# Sprite.net
KiCad netlist of a schematic drawn in EAGLE
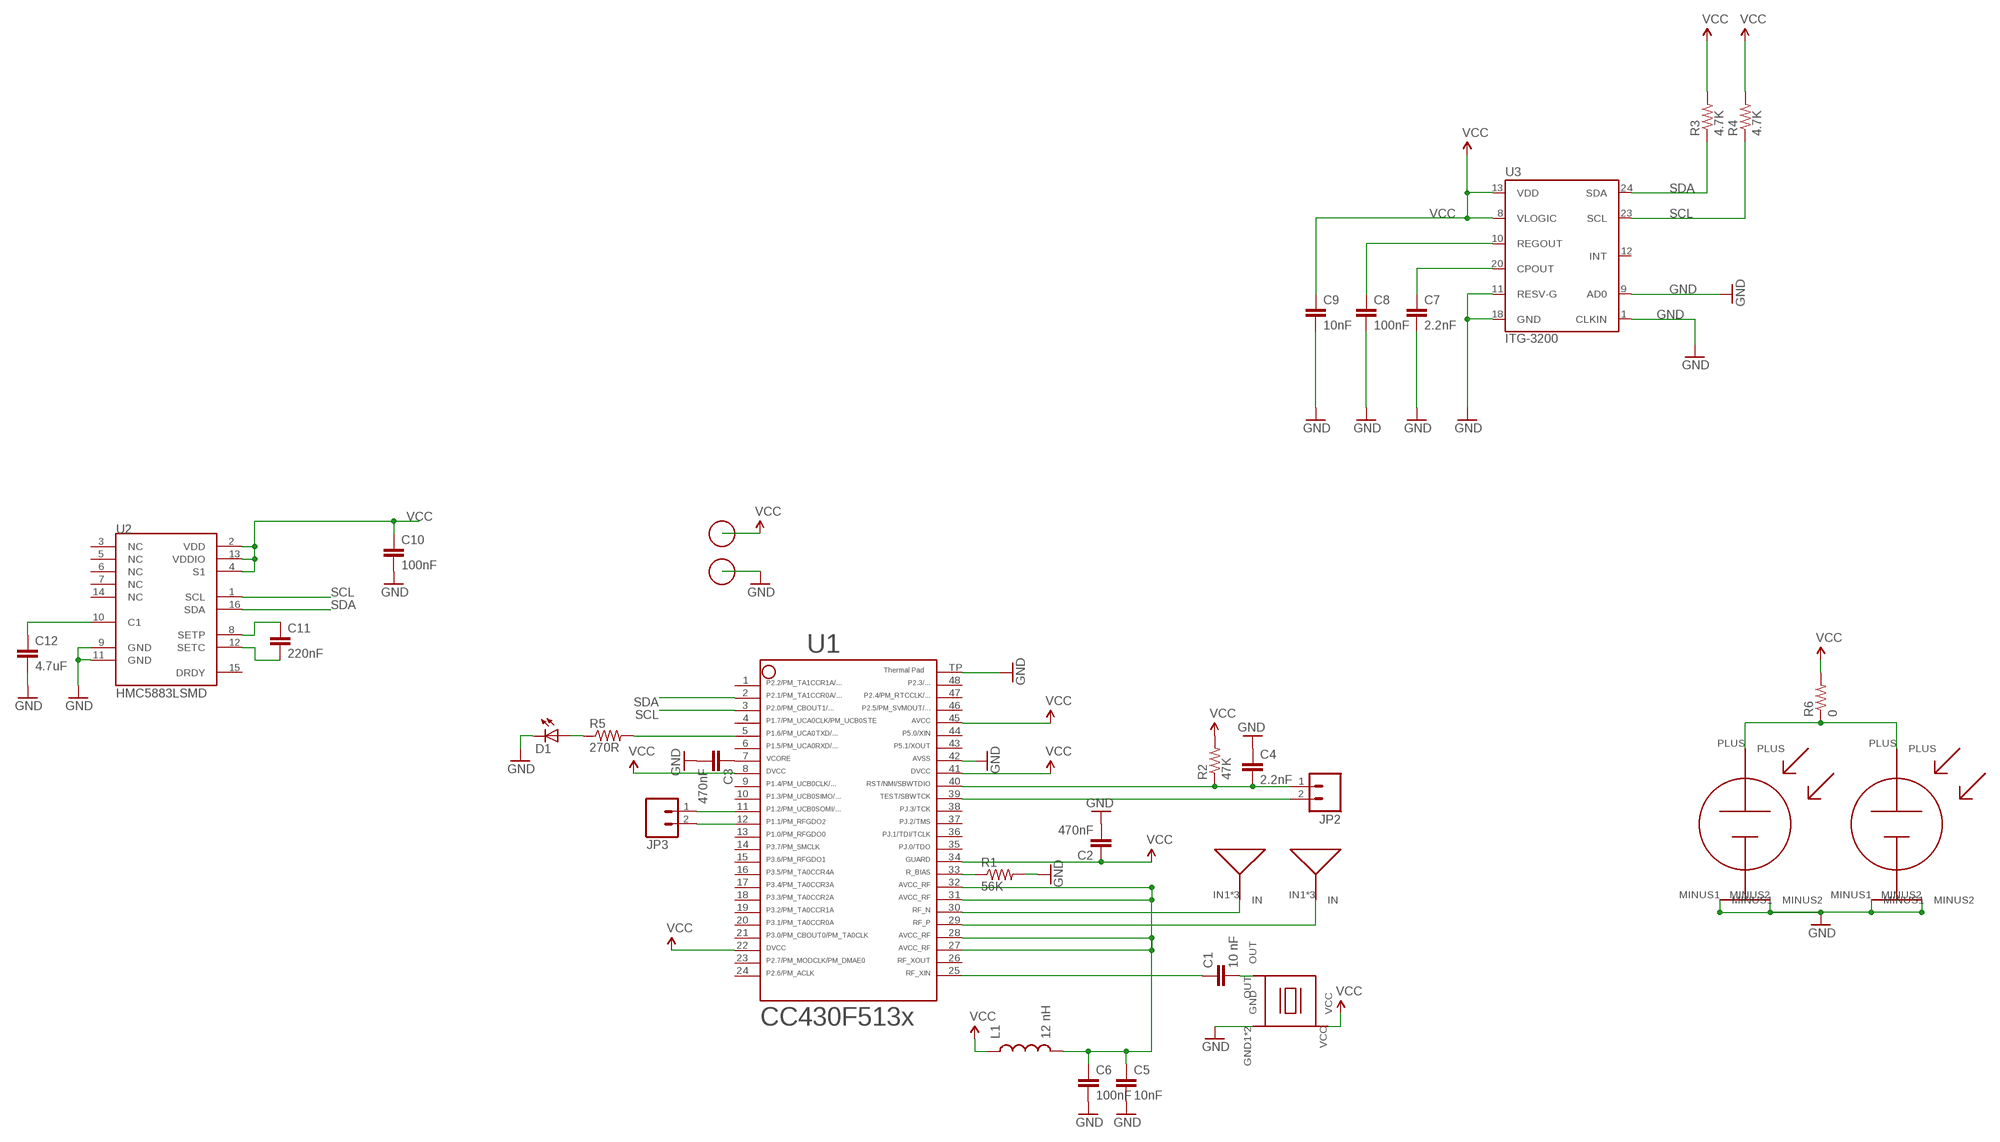
[diagram p0: schematic, sheet 1]

(export (version "E")
  (design (tool "Eeschema 10.0.6"))
  (components
    (comp (ref "ANT-N")
      (value "ANTENNA")
      (footprint "eagle-import:ANTENNA")
      (libsource (lib "eagle-import") (part "ANTENNA"))
    )
    (comp (ref "ANT-P")
      (value "ANTENNA")
      (footprint "eagle-import:ANTENNA")
      (libsource (lib "eagle-import") (part "ANTENNA"))
    )
    (comp (ref "C1")
      (value "10 nF")
      (footprint "eagle-import:0603-CAP")
      (libsource (lib "eagle-import") (part "CAP0603-CAP"))
    )
    (comp (ref "C2")
      (value "470nF")
      (footprint "eagle-import:0603-CAP")
      (libsource (lib "eagle-import") (part "CAP0603-CAP"))
    )
    (comp (ref "C3")
      (value "470nF")
      (footprint "eagle-import:0603-CAP")
      (libsource (lib "eagle-import") (part "CAP0603-CAP"))
    )
    (comp (ref "C4")
      (value "2.2nF")
      (footprint "eagle-import:0603-CAP")
      (libsource (lib "eagle-import") (part "CAP0603-CAP"))
    )
    (comp (ref "C5")
      (value "10nF")
      (footprint "eagle-import:0603-CAP")
      (libsource (lib "eagle-import") (part "CAP0603-CAP"))
    )
    (comp (ref "C6")
      (value "100nF")
      (footprint "eagle-import:0603-CAP")
      (libsource (lib "eagle-import") (part "CAP0603-CAP"))
    )
    (comp (ref "C7")
      (value "2.2nF")
      (footprint "eagle-import:0603-CAP")
      (libsource (lib "eagle-import") (part "CAP0603-CAP"))
    )
    (comp (ref "C8")
      (value "100nF")
      (footprint "eagle-import:0603-CAP")
      (libsource (lib "eagle-import") (part "CAP0603-CAP"))
    )
    (comp (ref "C9")
      (value "10nF")
      (footprint "eagle-import:0603-CAP")
      (libsource (lib "eagle-import") (part "CAP0603-CAP"))
    )
    (comp (ref "C10")
      (value "100nF")
      (footprint "eagle-import:0603-CAP")
      (libsource (lib "eagle-import") (part "CAP0603-CAP"))
    )
    (comp (ref "C11")
      (value "220nF")
      (footprint "eagle-import:0603-CAP")
      (libsource (lib "eagle-import") (part "CAP0603-CAP"))
    )
    (comp (ref "C12")
      (value "4.7uF")
      (footprint "eagle-import:0603-CAP")
      (libsource (lib "eagle-import") (part "CAP0603-CAP"))
    )
    (comp (ref "D1")
      (value "LED0603")
      (footprint "eagle-import:LED-0603")
      (libsource (lib "eagle-import") (part "LED0603"))
    )
    (comp (ref "JP2")
      (value "M02PTH")
      (footprint "eagle-import:1X02")
      (libsource (lib "eagle-import") (part "M02PTH"))
    )
    (comp (ref "JP3")
      (value "M02PTH")
      (footprint "eagle-import:1X02")
      (libsource (lib "eagle-import") (part "M02PTH"))
    )
    (comp (ref "L1")
      (value "12 nH")
      (footprint "eagle-import:0603")
      (libsource (lib "eagle-import") (part "INDUCTOR0603"))
    )
    (comp (ref "P1")
      (value "SPRITE_PIN")
      (footprint "eagle-import:SPRITE_PIN")
      (libsource (lib "eagle-import") (part "SPRITE_PIN"))
    )
    (comp (ref "P2")
      (value "SPRITE_PIN")
      (footprint "eagle-import:SPRITE_PIN")
      (libsource (lib "eagle-import") (part "SPRITE_PIN"))
    )
    (comp (ref "R1")
      (value "56K")
      (footprint "eagle-import:0603-RES")
      (libsource (lib "eagle-import") (part "RESISTOR0603-RES"))
    )
    (comp (ref "R2")
      (value "47K")
      (footprint "eagle-import:0603-RES")
      (libsource (lib "eagle-import") (part "RESISTOR0603-RES"))
    )
    (comp (ref "R3")
      (value "4.7K")
      (footprint "eagle-import:0603-RES")
      (libsource (lib "eagle-import") (part "RESISTOR0603-RES"))
    )
    (comp (ref "R4")
      (value "4.7K")
      (footprint "eagle-import:0603-RES")
      (libsource (lib "eagle-import") (part "RESISTOR0603-RES"))
    )
    (comp (ref "R5")
      (value "270R")
      (footprint "eagle-import:0603-RES")
      (libsource (lib "eagle-import") (part "RESISTOR0603-RES"))
    )
    (comp (ref "R6")
      (value "0")
      (footprint "eagle-import:R0805")
      (libsource (lib "eagle-import") (part "R-US_R0805"))
    )
    (comp (ref "S1")
      (value "TASC")
      (footprint "eagle-import:TASC")
      (libsource (lib "eagle-import") (part "TASC"))
    )
    (comp (ref "S2")
      (value "TASC")
      (footprint "eagle-import:TASC")
      (libsource (lib "eagle-import") (part "TASC"))
    )
    (comp (ref "U1")
      (value "CC430F5137")
      (footprint "eagle-import:RGZ48")
      (libsource (lib "eagle-import") (part "CC430F513X---RGZ48"))
    )
    (comp (ref "U2")
      (value "HMC5883LSMD")
      (footprint "eagle-import:16LPCC")
      (libsource (lib "eagle-import") (part "HMC5883LSMD"))
    )
    (comp (ref "U3")
      (value "ITG-3200")
      (footprint "eagle-import:QFN-24")
      (libsource (lib "eagle-import") (part "ITG-3200"))
    )
    (comp (ref "X1")
      (value "TCXO_7Z")
      (footprint "eagle-import:TXC_7Z")
      (libsource (lib "eagle-import") (part "TCXO_7Z"))
    )
  )
  (nets
    (net (code "1") (name "/SCL") (class "Default")
      (node (ref "R4") (pin "1") (pinfunction "1_1") (pintype "passive"))
      (node (ref "U1") (pin "3") (pinfunction "3_3") (pintype "bidirectional"))
      (node (ref "U2") (pin "1") (pinfunction "SCL_1") (pintype "bidirectional"))
      (node (ref "U3") (pin "23") (pinfunction "SCL_23") (pintype "bidirectional"))
    )
    (net (code "2") (name "/SDA") (class "Default")
      (node (ref "R3") (pin "1") (pinfunction "1_1") (pintype "passive"))
      (node (ref "U1") (pin "2") (pinfunction "2_2") (pintype "bidirectional"))
      (node (ref "U2") (pin "16") (pinfunction "SDA_16") (pintype "bidirectional"))
      (node (ref "U3") (pin "24") (pinfunction "SDA_24") (pintype "bidirectional"))
    )
    (net (code "3") (name "GND") (class "Default")
      (node (ref "C10") (pin "2") (pinfunction "2_2") (pintype "passive"))
      (node (ref "C12") (pin "2") (pinfunction "2_2") (pintype "passive"))
      (node (ref "C2") (pin "2") (pinfunction "2_2") (pintype "passive"))
      (node (ref "C3") (pin "2") (pinfunction "2_2") (pintype "passive"))
      (node (ref "C4") (pin "1") (pinfunction "1_1") (pintype "passive"))
      (node (ref "C5") (pin "2") (pinfunction "2_2") (pintype "passive"))
      (node (ref "C6") (pin "2") (pinfunction "2_2") (pintype "passive"))
      (node (ref "C7") (pin "2") (pinfunction "2_2") (pintype "passive"))
      (node (ref "C8") (pin "2") (pinfunction "2_2") (pintype "passive"))
      (node (ref "C9") (pin "2") (pinfunction "2_2") (pintype "passive"))
      (node (ref "D1") (pin "C") (pinfunction "C_C") (pintype "passive"))
      (node (ref "R1") (pin "2") (pinfunction "2_2") (pintype "passive"))
      (node (ref "S1") (pin "MINUS1") (pinfunction "MINUS1_MINUS1") (pintype "power_in"))
      (node (ref "S1") (pin "MINUS2") (pinfunction "MINUS2_MINUS2") (pintype "power_in"))
      (node (ref "S2") (pin "MINUS1") (pinfunction "MINUS1_MINUS1") (pintype "power_in"))
      (node (ref "S2") (pin "MINUS2") (pinfunction "MINUS2_MINUS2") (pintype "power_in"))
      (node (ref "U1") (pin "42") (pinfunction "42_42") (pintype "power_in"))
      (node (ref "U1") (pin "TP") (pinfunction "49_TP") (pintype "power_in"))
      (node (ref "U2") (pin "11") (pinfunction "GND_11") (pintype "bidirectional"))
      (node (ref "U2") (pin "9") (pinfunction "GND_9") (pintype "bidirectional"))
      (node (ref "U3") (pin "1") (pinfunction "CLKIN_1") (pintype "bidirectional"))
      (node (ref "U3") (pin "11") (pinfunction "RESV-G_11") (pintype "bidirectional"))
      (node (ref "U3") (pin "18") (pinfunction "GND_18") (pintype "bidirectional"))
      (node (ref "U3") (pin "9") (pinfunction "AD0_9") (pintype "bidirectional"))
      (node (ref "X1") (pin "GND1") (pinfunction "GND_GND1") (pintype "bidirectional"))
      (node (ref "X1") (pin "GND2") (pinfunction "GND_GND2") (pintype "bidirectional"))
    )
    (net (code "4") (name "Net-(ANT-N-IN-PadIN1)") (class "Default")
      (node (ref "ANT-N") (pin "IN1") (pinfunction "IN_IN1") (pintype "bidirectional"))
      (node (ref "ANT-N") (pin "IN2") (pinfunction "IN_IN2") (pintype "bidirectional"))
      (node (ref "ANT-N") (pin "IN3") (pinfunction "IN_IN3") (pintype "bidirectional"))
      (node (ref "U1") (pin "30") (pinfunction "30_30") (pintype "bidirectional"))
    )
    (net (code "5") (name "Net-(ANT-P-IN-PadIN1)") (class "Default")
      (node (ref "ANT-P") (pin "IN1") (pinfunction "IN_IN1") (pintype "bidirectional"))
      (node (ref "ANT-P") (pin "IN2") (pinfunction "IN_IN2") (pintype "bidirectional"))
      (node (ref "ANT-P") (pin "IN3") (pinfunction "IN_IN3") (pintype "bidirectional"))
      (node (ref "U1") (pin "29") (pinfunction "29_29") (pintype "bidirectional"))
    )
    (net (code "6") (name "Net-(C1-Pad1)") (class "Default")
      (node (ref "C1") (pin "1") (pinfunction "1_1") (pintype "passive"))
      (node (ref "U1") (pin "25") (pinfunction "25_25") (pintype "input"))
    )
    (net (code "7") (name "Net-(C1-Pad2)") (class "Default")
      (node (ref "C1") (pin "2") (pinfunction "2_2") (pintype "passive"))
      (node (ref "X1") (pin "OUT") (pinfunction "OUT_OUT") (pintype "bidirectional"))
    )
    (net (code "8") (name "Net-(C3-Pad1)") (class "Default")
      (node (ref "C3") (pin "1") (pinfunction "1_1") (pintype "passive"))
      (node (ref "U1") (pin "7") (pinfunction "7_7") (pintype "power_in"))
    )
    (net (code "9") (name "Net-(C4-Pad2)") (class "Default")
      (node (ref "C4") (pin "2") (pinfunction "2_2") (pintype "passive"))
      (node (ref "JP2") (pin "1") (pinfunction "1_1") (pintype "passive"))
      (node (ref "R2") (pin "1") (pinfunction "1_1") (pintype "passive"))
      (node (ref "U1") (pin "40") (pinfunction "40_40") (pintype "bidirectional"))
    )
    (net (code "10") (name "Net-(C5-Pad1)") (class "Default")
      (node (ref "C5") (pin "1") (pinfunction "1_1") (pintype "passive"))
      (node (ref "C6") (pin "1") (pinfunction "1_1") (pintype "passive"))
      (node (ref "L1") (pin "2") (pinfunction "2_2") (pintype "passive"))
      (node (ref "U1") (pin "27") (pinfunction "27_27") (pintype "power_in"))
      (node (ref "U1") (pin "28") (pinfunction "28_28") (pintype "bidirectional"))
      (node (ref "U1") (pin "31") (pinfunction "31_31") (pintype "power_in"))
      (node (ref "U1") (pin "32") (pinfunction "32_32") (pintype "power_in"))
    )
    (net (code "11") (name "Net-(D1-PadA)") (class "Default")
      (node (ref "D1") (pin "A") (pinfunction "A_A") (pintype "passive"))
      (node (ref "R5") (pin "1") (pinfunction "1_1") (pintype "passive"))
    )
    (net (code "12") (name "Net-(JP2-Pad2)") (class "Default")
      (node (ref "JP2") (pin "2") (pinfunction "2_2") (pintype "passive"))
      (node (ref "U1") (pin "39") (pinfunction "39_39") (pintype "input"))
    )
    (net (code "13") (name "Net-(JP3-Pad1)") (class "Default")
      (node (ref "JP3") (pin "1") (pinfunction "1_1") (pintype "passive"))
      (node (ref "U1") (pin "11") (pinfunction "11_11") (pintype "bidirectional"))
    )
    (net (code "14") (name "Net-(JP3-Pad2)") (class "Default")
      (node (ref "JP3") (pin "2") (pinfunction "2_2") (pintype "passive"))
      (node (ref "U1") (pin "12") (pinfunction "12_12") (pintype "bidirectional"))
    )
    (net (code "15") (name "Net-(R1-Pad1)") (class "Default")
      (node (ref "R1") (pin "1") (pinfunction "1_1") (pintype "passive"))
      (node (ref "U1") (pin "33") (pinfunction "33_33") (pintype "power_in"))
    )
    (net (code "16") (name "Net-(R5-Pad2)") (class "Default")
      (node (ref "R5") (pin "2") (pinfunction "2_2") (pintype "passive"))
      (node (ref "U1") (pin "5") (pinfunction "5_5") (pintype "bidirectional"))
    )
    (net (code "17") (name "Net-(R6-Pad1)") (class "Default")
      (node (ref "R6") (pin "1") (pinfunction "1_1") (pintype "passive"))
      (node (ref "S1") (pin "PLUS") (pinfunction "PLUS_PLUS") (pintype "power_in"))
      (node (ref "S2") (pin "PLUS") (pinfunction "PLUS_PLUS") (pintype "power_in"))
    )
    (net (code "18") (name "Net-(U2-C1)") (class "Default")
      (node (ref "C12") (pin "1") (pinfunction "1_1") (pintype "passive"))
      (node (ref "U2") (pin "10") (pinfunction "C1_10") (pintype "bidirectional"))
    )
    (net (code "19") (name "Net-(U2-SETC)") (class "Default")
      (node (ref "C11") (pin "2") (pinfunction "2_2") (pintype "passive"))
      (node (ref "U2") (pin "12") (pinfunction "SETC_12") (pintype "bidirectional"))
    )
    (net (code "20") (name "Net-(U2-SETP)") (class "Default")
      (node (ref "C11") (pin "1") (pinfunction "1_1") (pintype "passive"))
      (node (ref "U2") (pin "8") (pinfunction "SETP_8") (pintype "bidirectional"))
    )
    (net (code "21") (name "Net-(U3-CPOUT)") (class "Default")
      (node (ref "C7") (pin "1") (pinfunction "1_1") (pintype "passive"))
      (node (ref "U3") (pin "20") (pinfunction "CPOUT_20") (pintype "bidirectional"))
    )
    (net (code "22") (name "Net-(U3-REGOUT)") (class "Default")
      (node (ref "C8") (pin "1") (pinfunction "1_1") (pintype "passive"))
      (node (ref "U3") (pin "10") (pinfunction "REGOUT_10") (pintype "bidirectional"))
    )
    (net (code "23") (name "VCC") (class "Default")
      (node (ref "C10") (pin "1") (pinfunction "1_1") (pintype "passive"))
      (node (ref "C2") (pin "1") (pinfunction "1_1") (pintype "passive"))
      (node (ref "C9") (pin "1") (pinfunction "1_1") (pintype "passive"))
      (node (ref "L1") (pin "1") (pinfunction "1_1") (pintype "passive"))
      (node (ref "R2") (pin "2") (pinfunction "2_2") (pintype "passive"))
      (node (ref "R3") (pin "2") (pinfunction "2_2") (pintype "passive"))
      (node (ref "R4") (pin "2") (pinfunction "2_2") (pintype "passive"))
      (node (ref "R6") (pin "2") (pinfunction "2_2") (pintype "passive"))
      (node (ref "U1") (pin "22") (pinfunction "22_22") (pintype "power_in"))
      (node (ref "U1") (pin "34") (pinfunction "34_34") (pintype "power_in"))
      (node (ref "U1") (pin "41") (pinfunction "41_41") (pintype "power_in"))
      (node (ref "U1") (pin "45") (pinfunction "45_45") (pintype "input"))
      (node (ref "U1") (pin "8") (pinfunction "8_8") (pintype "power_in"))
      (node (ref "U2") (pin "13") (pinfunction "VDDIO_13") (pintype "bidirectional"))
      (node (ref "U2") (pin "2") (pinfunction "VDD_2") (pintype "bidirectional"))
      (node (ref "U2") (pin "4") (pinfunction "S1_4") (pintype "bidirectional"))
      (node (ref "U3") (pin "13") (pinfunction "VDD_13") (pintype "bidirectional"))
      (node (ref "U3") (pin "8") (pinfunction "VLOGIC_8") (pintype "bidirectional"))
      (node (ref "X1") (pin "VCC") (pinfunction "VCC_VCC") (pintype "bidirectional"))
    )
    (net (code "24") (name "unconnected-(U1-Pad1)") (class "Default")
      (node (ref "U1") (pin "1") (pinfunction "1_1") (pintype "bidirectional"))
    )
    (net (code "25") (name "unconnected-(U1-Pad4)") (class "Default")
      (node (ref "U1") (pin "4") (pinfunction "4_4") (pintype "bidirectional"))
    )
    (net (code "26") (name "unconnected-(U1-Pad6)") (class "Default")
      (node (ref "U1") (pin "6") (pinfunction "6_6") (pintype "bidirectional"))
    )
    (net (code "27") (name "unconnected-(U1-Pad9)") (class "Default")
      (node (ref "U1") (pin "9") (pinfunction "9_9") (pintype "bidirectional"))
    )
    (net (code "28") (name "unconnected-(U1-Pad10)") (class "Default")
      (node (ref "U1") (pin "10") (pinfunction "10_10") (pintype "bidirectional"))
    )
    (net (code "29") (name "unconnected-(U1-Pad13)") (class "Default")
      (node (ref "U1") (pin "13") (pinfunction "13_13") (pintype "bidirectional"))
    )
    (net (code "30") (name "unconnected-(U1-Pad14)") (class "Default")
      (node (ref "U1") (pin "14") (pinfunction "14_14") (pintype "bidirectional"))
    )
    (net (code "31") (name "unconnected-(U1-Pad15)") (class "Default")
      (node (ref "U1") (pin "15") (pinfunction "15_15") (pintype "bidirectional"))
    )
    (net (code "32") (name "unconnected-(U1-Pad16)") (class "Default")
      (node (ref "U1") (pin "16") (pinfunction "16_16") (pintype "bidirectional"))
    )
    (net (code "33") (name "unconnected-(U1-Pad17)") (class "Default")
      (node (ref "U1") (pin "17") (pinfunction "17_17") (pintype "bidirectional"))
    )
    (net (code "34") (name "unconnected-(U1-Pad18)") (class "Default")
      (node (ref "U1") (pin "18") (pinfunction "18_18") (pintype "bidirectional"))
    )
    (net (code "35") (name "unconnected-(U1-Pad19)") (class "Default")
      (node (ref "U1") (pin "19") (pinfunction "19_19") (pintype "bidirectional"))
    )
    (net (code "36") (name "unconnected-(U1-Pad20)") (class "Default")
      (node (ref "U1") (pin "20") (pinfunction "20_20") (pintype "bidirectional"))
    )
    (net (code "37") (name "unconnected-(U1-Pad21)") (class "Default")
      (node (ref "U1") (pin "21") (pinfunction "21_21") (pintype "bidirectional"))
    )
    (net (code "38") (name "unconnected-(U1-Pad23)") (class "Default")
      (node (ref "U1") (pin "23") (pinfunction "23_23") (pintype "bidirectional"))
    )
    (net (code "39") (name "unconnected-(U1-Pad24)") (class "Default")
      (node (ref "U1") (pin "24") (pinfunction "24_24") (pintype "bidirectional"))
    )
    (net (code "40") (name "unconnected-(U1-Pad26)") (class "Default")
      (node (ref "U1") (pin "26") (pinfunction "26_26") (pintype "output"))
    )
    (net (code "41") (name "unconnected-(U1-Pad35)") (class "Default")
      (node (ref "U1") (pin "35") (pinfunction "35_35") (pintype "bidirectional"))
    )
    (net (code "42") (name "unconnected-(U1-Pad36)") (class "Default")
      (node (ref "U1") (pin "36") (pinfunction "36_36") (pintype "bidirectional"))
    )
    (net (code "43") (name "unconnected-(U1-Pad37)") (class "Default")
      (node (ref "U1") (pin "37") (pinfunction "37_37") (pintype "bidirectional"))
    )
    (net (code "44") (name "unconnected-(U1-Pad38)") (class "Default")
      (node (ref "U1") (pin "38") (pinfunction "38_38") (pintype "bidirectional"))
    )
    (net (code "45") (name "unconnected-(U1-Pad43)") (class "Default")
      (node (ref "U1") (pin "43") (pinfunction "43_43") (pintype "input"))
    )
    (net (code "46") (name "unconnected-(U1-Pad44)") (class "Default")
      (node (ref "U1") (pin "44") (pinfunction "44_44") (pintype "input"))
    )
    (net (code "47") (name "unconnected-(U1-Pad46)") (class "Default")
      (node (ref "U1") (pin "46") (pinfunction "46_46") (pintype "bidirectional"))
    )
    (net (code "48") (name "unconnected-(U1-Pad47)") (class "Default")
      (node (ref "U1") (pin "47") (pinfunction "47_47") (pintype "input"))
    )
    (net (code "49") (name "unconnected-(U1-Pad48)") (class "Default")
      (node (ref "U1") (pin "48") (pinfunction "48_48") (pintype "bidirectional"))
    )
    (net (code "50") (name "unconnected-(U2-DRDY-Pad15)") (class "Default")
      (node (ref "U2") (pin "15") (pinfunction "DRDY_15") (pintype "bidirectional"))
    )
    (net (code "51") (name "unconnected-(U2-NC-Pad3)") (class "Default")
      (node (ref "U2") (pin "3") (pinfunction "NC_3") (pintype "bidirectional"))
    )
    (net (code "52") (name "unconnected-(U2-NC-Pad5)") (class "Default")
      (node (ref "U2") (pin "5") (pinfunction "NC_5") (pintype "bidirectional"))
    )
    (net (code "53") (name "unconnected-(U2-NC-Pad6)") (class "Default")
      (node (ref "U2") (pin "6") (pinfunction "NC_6") (pintype "bidirectional"))
    )
    (net (code "54") (name "unconnected-(U2-NC-Pad7)") (class "Default")
      (node (ref "U2") (pin "7") (pinfunction "NC_7") (pintype "bidirectional"))
    )
    (net (code "55") (name "unconnected-(U2-NC-Pad14)") (class "Default")
      (node (ref "U2") (pin "14") (pinfunction "NC_14") (pintype "bidirectional"))
    )
    (net (code "56") (name "unconnected-(U3-INT-Pad12)") (class "Default")
      (node (ref "U3") (pin "12") (pinfunction "INT_12") (pintype "bidirectional"))
    )
  )
)
